# CAN.net
KiCad netlist of a schematic drawn in Altium Designer
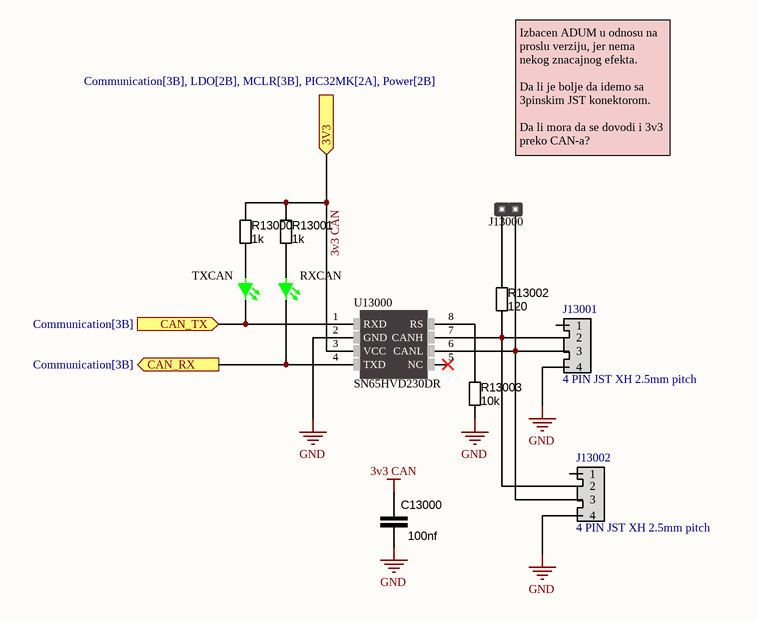
[diagram p0: CAN.SchDoc]

(export (version "E")
  (design (tool "Eeschema 10.0.6"))
  (components
    (comp (ref "C13000")
      (value "100nf")
      (footprint "CAP_0603")
      (description "CAP CER 100nF 0603 25V X7R")
      (libsource (lib "CapacitorsIntegrated") (part "C000007"))
    )
    (comp (ref "J13000") (value "*") (footprint "HM1x2") (libsource (lib "motion_board") (part "HEADER_1x2")))
    (comp (ref "J13001")
      (value "4 PIN JST XH 2.5mm pitch")
      (footprint "Connectors:JST4PIN")
      (libsource (lib "Connectors") (part "JST4PIN"))
    )
    (comp (ref "J13002")
      (value "4 PIN JST XH 2.5mm pitch")
      (footprint "Connectors:JST4PIN")
      (libsource (lib "Connectors") (part "JST4PIN"))
    )
    (comp (ref "R13000")
      (value "1k")
      (footprint "RES_0603")
      (description "RES 1k OHM 1% 1/10W 0603")
      (libsource (lib "ResistorsIntegrated") (part "R000004"))
    )
    (comp (ref "R13001")
      (value "1k")
      (footprint "RES_0603")
      (description "RES 1k OHM 1% 1/10W 0603")
      (libsource (lib "ResistorsIntegrated") (part "R000004"))
    )
    (comp (ref "R13002")
      (value "120")
      (footprint "RES_0603")
      (description "RES 120 OHM 1% 1/10W 0603")
      (libsource (lib "ResistorsIntegrated") (part "R000004"))
    )
    (comp (ref "R13003")
      (value "10k")
      (footprint "RES_0603")
      (description "RES 10k OHM 1% 1/10W 0603")
      (libsource (lib "ResistorsIntegrated") (part "R000004"))
    )
    (comp (ref "RXCAN")
      (value "GREEN LED")
      (footprint "DIOC1608X04N")
      (description "LED GREEN DIFFUSED 0603 SMD")
      (libsource (lib "Miscellaneous_Lib1") (part "00000001"))
    )
    (comp (ref "TXCAN")
      (value "GREEN LED")
      (footprint "DIOC1608X04N")
      (description "LED GREEN DIFFUSED 0603 SMD")
      (libsource (lib "Miscellaneous_Lib1") (part "00000001"))
    )
    (comp (ref "U13000")
      (value "SN65HVD230DR")
      (footprint "SOIC-8")
      (description "IC EMC CAN TRANSCEIVER 8-SOIC")
      (libsource (lib "motion_board") (part "SN65HVD230"))
    )
  )
  (nets
    (net (code "1") (name "/CAN_RX") (class "Default")
      (node (ref "RXCAN") (pin "2") (pinfunction "2_2") (pintype "passive"))
      (node (ref "U13000") (pin "4") (pinfunction "TXD_4") (pintype "passive"))
    )
    (net (code "2") (name "/CAN_TX") (class "Default")
      (node (ref "TXCAN") (pin "2") (pinfunction "2_2") (pintype "passive"))
      (node (ref "U13000") (pin "1") (pinfunction "RXD_1") (pintype "passive"))
    )
    (net (code "3") (name "3v3 CAN") (class "Default")
      (node (ref "C13000") (pin "2") (pinfunction "2_2") (pintype "passive"))
      (node (ref "R13000") (pin "2") (pinfunction "2_2") (pintype "passive"))
      (node (ref "R13001") (pin "2") (pinfunction "2_2") (pintype "passive"))
      (node (ref "U13000") (pin "3") (pinfunction "VCC_3") (pintype "passive"))
    )
    (net (code "4") (name "GND") (class "Default")
      (node (ref "C13000") (pin "1") (pinfunction "1_1") (pintype "passive"))
      (node (ref "J13001") (pin "4") (pinfunction "4_4") (pintype "passive"))
      (node (ref "J13002") (pin "4") (pinfunction "4_4") (pintype "passive"))
      (node (ref "R13003") (pin "1") (pinfunction "1_1") (pintype "passive"))
      (node (ref "U13000") (pin "2") (pinfunction "GND_2") (pintype "passive"))
    )
    (net (code "5") (name "Net-(J13000-Pad1)") (class "Default")
      (node (ref "J13000") (pin "1") (pinfunction "1_1") (pintype "passive"))
      (node (ref "R13002") (pin "2") (pinfunction "2_2") (pintype "passive"))
    )
    (net (code "6") (name "Net-(R13000-Pad1)") (class "Default")
      (node (ref "R13000") (pin "1") (pinfunction "1_1") (pintype "passive"))
      (node (ref "TXCAN") (pin "1") (pinfunction "1_1") (pintype "passive"))
    )
    (net (code "7") (name "Net-(R13001-Pad1)") (class "Default")
      (node (ref "R13001") (pin "1") (pinfunction "1_1") (pintype "passive"))
      (node (ref "RXCAN") (pin "1") (pinfunction "1_1") (pintype "passive"))
    )
    (net (code "8") (name "Net-(U13000-CANH)") (class "Default")
      (node (ref "J13001") (pin "2") (pinfunction "2_2") (pintype "passive"))
      (node (ref "J13002") (pin "2") (pinfunction "2_2") (pintype "passive"))
      (node (ref "R13002") (pin "1") (pinfunction "1_1") (pintype "passive"))
      (node (ref "U13000") (pin "7") (pinfunction "CANH_7") (pintype "passive"))
    )
    (net (code "9") (name "Net-(U13000-CANL)") (class "Default")
      (node (ref "J13000") (pin "2") (pinfunction "1_2") (pintype "passive"))
      (node (ref "J13001") (pin "3") (pinfunction "3_3") (pintype "passive"))
      (node (ref "J13002") (pin "3") (pinfunction "3_3") (pintype "passive"))
      (node (ref "U13000") (pin "6") (pinfunction "CANL_6") (pintype "passive"))
    )
    (net (code "10") (name "Net-(U13000-RS)") (class "Default")
      (node (ref "R13003") (pin "2") (pinfunction "2_2") (pintype "passive"))
      (node (ref "U13000") (pin "8") (pinfunction "RS_8") (pintype "passive"))
    )
    (net (code "11") (name "unconnected-(J13001-Pad1)") (class "Default")
      (node (ref "J13001") (pin "1") (pinfunction "1_1") (pintype "passive"))
    )
    (net (code "12") (name "unconnected-(J13002-Pad1)") (class "Default")
      (node (ref "J13002") (pin "1") (pinfunction "1_1") (pintype "passive"))
    )
    (net (code "13") (name "unconnected-(U13000-NC-Pad5)") (class "Default")
      (node (ref "U13000") (pin "5") (pinfunction "NC_5") (pintype "passive+no_connect"))
    )
  )
)
